# Wetterstation.net
KiCad netlist of a schematic drawn in EAGLE
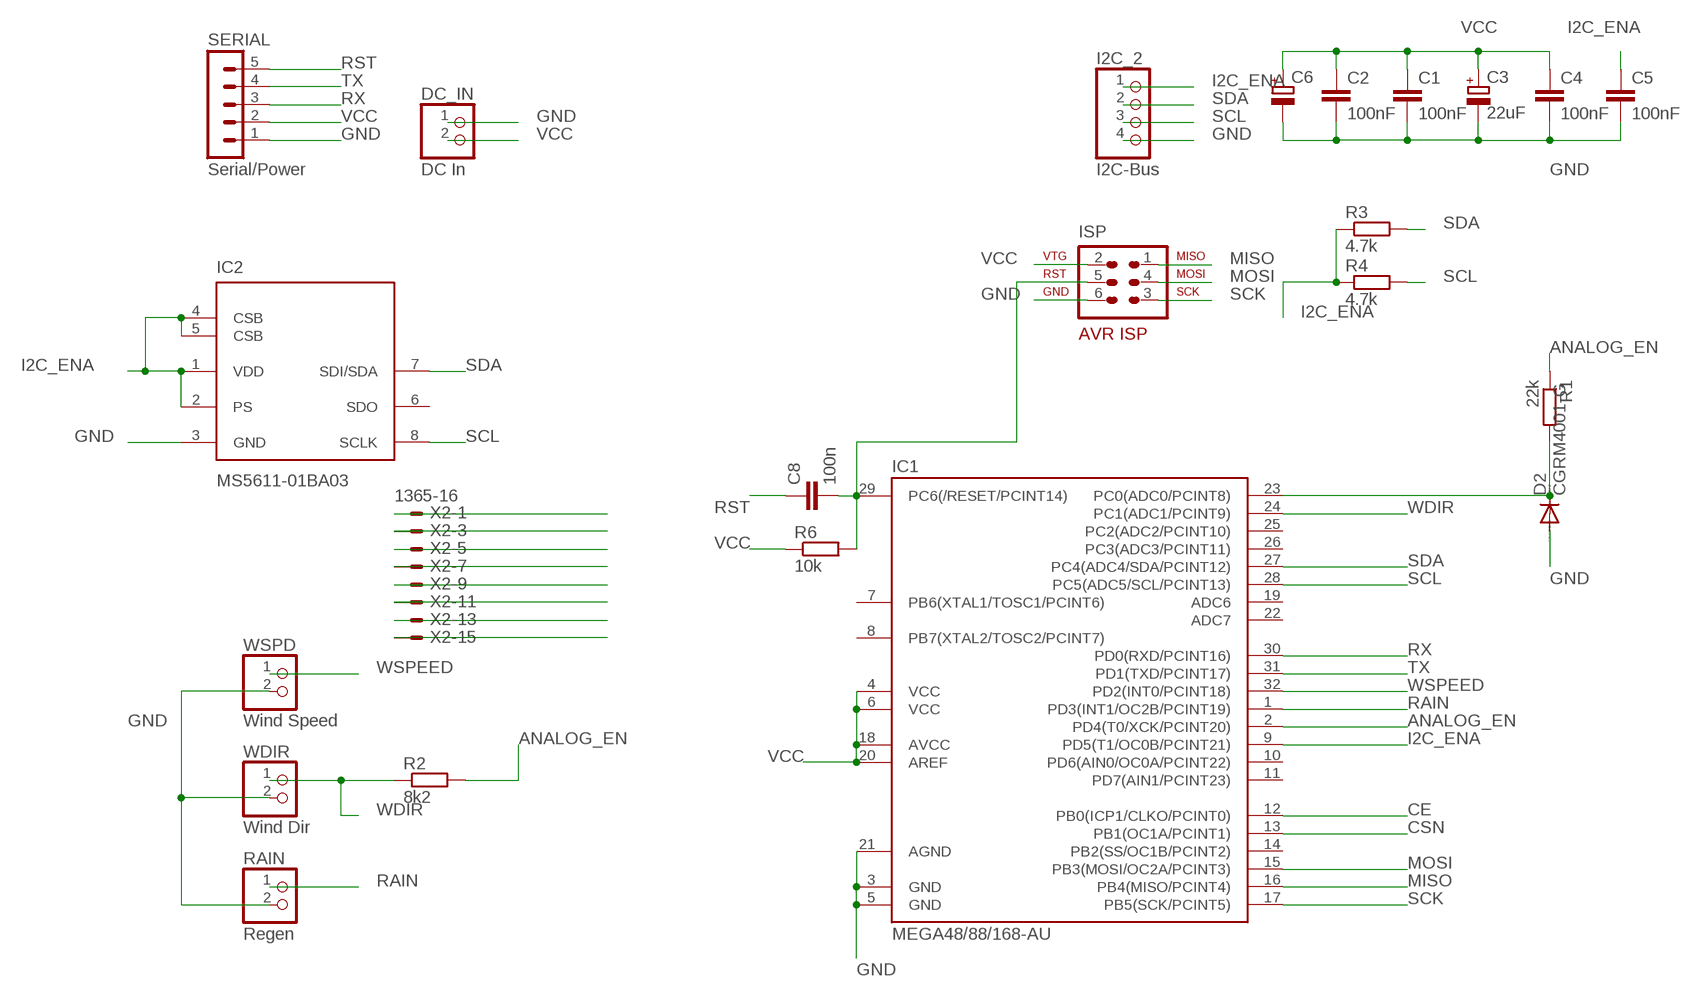
[diagram p0: schematic, sheet 1]

(export (version "E")
  (design (tool "Eeschema 10.0.6"))
  (components
    (comp (ref "C1")
      (value "100nF")
      (footprint "eagle-import:C0805")
      (libsource (lib "eagle-import") (part "C-EUC0805"))
    )
    (comp (ref "C2")
      (value "100nF")
      (footprint "eagle-import:C0805")
      (libsource (lib "eagle-import") (part "C-EUC0805"))
    )
    (comp (ref "C3")
      (value "22uF")
      (footprint "eagle-import:SMC_C")
      (libsource (lib "eagle-import") (part "resistor_CPOL-EUSMCC"))
    )
    (comp (ref "C4")
      (value "100nF")
      (footprint "eagle-import:C0805")
      (libsource (lib "eagle-import") (part "C-EUC0805"))
    )
    (comp (ref "C5")
      (value "100nF")
      (footprint "eagle-import:C0805")
      (libsource (lib "eagle-import") (part "C-EUC0805"))
    )
    (comp (ref "C6")
      (value "CPOL-EUB/3528-21R")
      (footprint "eagle-import:B_3528-21R")
      (libsource (lib "eagle-import") (part "CPOL-EUB/3528-21R"))
    )
    (comp (ref "C8")
      (value "100n")
      (footprint "eagle-import:C0805")
      (libsource (lib "eagle-import") (part "C-EUC0805"))
    )
    (comp (ref "D2")
      (value "CGRM4001-G")
      (footprint "eagle-import:SOD-123_MINI-SMA")
      (libsource (lib "eagle-import") (part "CGRM400-G1"))
    )
    (comp (ref "DC_IN")
      (value "DC In")
      (footprint "eagle-import:1X02")
      (libsource (lib "eagle-import") (part "PINHD-1X2"))
    )
    (comp (ref "I2C_2")
      (value "I2C-Bus")
      (footprint "eagle-import:1X04")
      (libsource (lib "eagle-import") (part "PINHD-1X4"))
    )
    (comp (ref "IC1")
      (value "MEGA48/88/168-AU")
      (footprint "eagle-import:TQFP32-08")
      (libsource (lib "eagle-import") (part "MEGA48/88/168-AU"))
    )
    (comp (ref "IC2")
      (value "MS5611-01BA03")
      (footprint "eagle-import:SON125P300X500X100-8N")
      (libsource (lib "eagle-import") (part "MS5611-01BA03"))
    )
    (comp (ref "ISP")
      (value "AVR-ISP-6")
      (footprint "eagle-import:AVR-ISP-6")
      (libsource (lib "eagle-import") (part "AVR-ISP-6"))
    )
    (comp (ref "R1")
      (value "22k")
      (footprint "eagle-import:R1206")
      (libsource (lib "eagle-import") (part "R-EU_R1206"))
    )
    (comp (ref "R2")
      (value "8k2")
      (footprint "eagle-import:R1206")
      (libsource (lib "eagle-import") (part "R-EU_R1206"))
    )
    (comp (ref "R3")
      (value "4.7k")
      (footprint "eagle-import:R1206")
      (libsource (lib "eagle-import") (part "R-EU_R1206"))
    )
    (comp (ref "R4")
      (value "4.7k")
      (footprint "eagle-import:R1206")
      (libsource (lib "eagle-import") (part "R-EU_R1206"))
    )
    (comp (ref "R6")
      (value "10k")
      (footprint "eagle-import:R1206")
      (libsource (lib "eagle-import") (part "R-EU_R1206"))
    )
    (comp (ref "RAIN")
      (value "Regen")
      (footprint "eagle-import:1X02")
      (libsource (lib "eagle-import") (part "PINHD-1X2"))
    )
    (comp (ref "SERIAL")
      (value "Serial/Power")
      (footprint "eagle-import:MA05-1")
      (libsource (lib "eagle-import") (part "MA05-1"))
    )
    (comp (ref "WDIR")
      (value "Wind Dir")
      (footprint "eagle-import:1X02")
      (libsource (lib "eagle-import") (part "PINHD-1X2"))
    )
    (comp (ref "WSPD")
      (value "Wind Speed")
      (footprint "eagle-import:1X02")
      (libsource (lib "eagle-import") (part "PINHD-1X2"))
    )
    (comp (ref "X2")
      (value "1365-16")
      (footprint "eagle-import:1365-16")
      (libsource (lib "eagle-import") (part "1365-16"))
    )
  )
  (nets
    (net (code "1") (name "/ANALOG_EN") (class "Default")
      (node (ref "IC1") (pin "2") (pinfunction "PD4(T0/XCK/PCINT20)_2") (pintype "bidirectional"))
      (node (ref "R1") (pin "1") (pinfunction "1_1") (pintype "passive"))
      (node (ref "R2") (pin "2") (pinfunction "2_2") (pintype "passive"))
    )
    (net (code "2") (name "/CE") (class "Default")
      (node (ref "IC1") (pin "12") (pinfunction "PB0(ICP1/CLKO/PCINT0)_12") (pintype "bidirectional"))
      (node (ref "X2") (pin "3") (pinfunction "S_3") (pintype "passive"))
    )
    (net (code "3") (name "/CSN") (class "Default")
      (node (ref "IC1") (pin "13") (pinfunction "PB1(OC1A/PCINT1)_13") (pintype "bidirectional"))
      (node (ref "X2") (pin "5") (pinfunction "S_5") (pintype "passive"))
    )
    (net (code "4") (name "/GND") (class "Default")
      (node (ref "C1") (pin "2") (pinfunction "2_2") (pintype "passive"))
      (node (ref "C2") (pin "2") (pinfunction "2_2") (pintype "passive"))
      (node (ref "C3") (pin "-") (pinfunction "-_-") (pintype "passive"))
      (node (ref "C4") (pin "2") (pinfunction "2_2") (pintype "passive"))
      (node (ref "C5") (pin "2") (pinfunction "2_2") (pintype "passive"))
      (node (ref "C6") (pin "-") (pinfunction "-_-") (pintype "passive"))
      (node (ref "D2") (pin "A") (pinfunction "A_A") (pintype "passive"))
      (node (ref "DC_IN") (pin "1") (pinfunction "1_1") (pintype "passive"))
      (node (ref "I2C_2") (pin "4") (pinfunction "4_4") (pintype "passive"))
      (node (ref "IC1") (pin "21") (pinfunction "AGND_21") (pintype "power_in"))
      (node (ref "IC1") (pin "3") (pinfunction "GND_3") (pintype "power_in"))
      (node (ref "IC1") (pin "5") (pinfunction "GND_5") (pintype "power_in"))
      (node (ref "IC2") (pin "3") (pinfunction "GND_3") (pintype "power_in"))
      (node (ref "ISP") (pin "6") (pinfunction "6_6") (pintype "passive"))
      (node (ref "RAIN") (pin "2") (pinfunction "2_2") (pintype "passive"))
      (node (ref "SERIAL") (pin "1") (pinfunction "1_1") (pintype "passive"))
      (node (ref "WDIR") (pin "2") (pinfunction "2_2") (pintype "passive"))
      (node (ref "WSPD") (pin "2") (pinfunction "2_2") (pintype "passive"))
      (node (ref "X2") (pin "15") (pinfunction "S_15") (pintype "passive"))
    )
    (net (code "5") (name "/I2C_ENA") (class "Default")
      (node (ref "C5") (pin "1") (pinfunction "1_1") (pintype "passive"))
      (node (ref "I2C_2") (pin "1") (pinfunction "1_1") (pintype "passive"))
      (node (ref "IC1") (pin "9") (pinfunction "PD5(T1/OC0B/PCINT21)_9") (pintype "bidirectional"))
      (node (ref "IC2") (pin "1") (pinfunction "VDD_1") (pintype "power_in"))
      (node (ref "IC2") (pin "2") (pinfunction "PS_2") (pintype "input"))
      (node (ref "IC2") (pin "4") (pinfunction "CSB_4") (pintype "input"))
      (node (ref "IC2") (pin "5") (pinfunction "CSB_5") (pintype "input"))
      (node (ref "R3") (pin "1") (pinfunction "1_1") (pintype "passive"))
      (node (ref "R4") (pin "1") (pinfunction "1_1") (pintype "passive"))
    )
    (net (code "6") (name "/MISO") (class "Default")
      (node (ref "IC1") (pin "16") (pinfunction "PB4(MISO/PCINT4)_16") (pintype "bidirectional"))
      (node (ref "ISP") (pin "1") (pinfunction "1_1") (pintype "passive"))
      (node (ref "X2") (pin "11") (pinfunction "S_11") (pintype "passive"))
    )
    (net (code "7") (name "/MOSI") (class "Default")
      (node (ref "IC1") (pin "15") (pinfunction "PB3(MOSI/OC2A/PCINT3)_15") (pintype "bidirectional"))
      (node (ref "ISP") (pin "4") (pinfunction "4_4") (pintype "passive"))
      (node (ref "X2") (pin "9") (pinfunction "S_9") (pintype "passive"))
    )
    (net (code "8") (name "/RAIN") (class "Default")
      (node (ref "IC1") (pin "1") (pinfunction "PD3(INT1/OC2B/PCINT19)_1") (pintype "bidirectional"))
      (node (ref "RAIN") (pin "1") (pinfunction "1_1") (pintype "passive"))
    )
    (net (code "9") (name "/RST") (class "Default")
      (node (ref "C8") (pin "1") (pinfunction "1_1") (pintype "passive"))
      (node (ref "SERIAL") (pin "5") (pinfunction "5_5") (pintype "passive"))
    )
    (net (code "10") (name "/RX") (class "Default")
      (node (ref "IC1") (pin "30") (pinfunction "PD0(RXD/PCINT16)_30") (pintype "bidirectional"))
      (node (ref "SERIAL") (pin "3") (pinfunction "3_3") (pintype "passive"))
    )
    (net (code "11") (name "/SCK") (class "Default")
      (node (ref "IC1") (pin "17") (pinfunction "PB5(SCK/PCINT5)_17") (pintype "bidirectional"))
      (node (ref "ISP") (pin "3") (pinfunction "3_3") (pintype "passive"))
      (node (ref "X2") (pin "7") (pinfunction "S_7") (pintype "passive"))
    )
    (net (code "12") (name "/SCL") (class "Default")
      (node (ref "I2C_2") (pin "3") (pinfunction "3_3") (pintype "passive"))
      (node (ref "IC1") (pin "28") (pinfunction "PC5(ADC5/SCL/PCINT13)_28") (pintype "bidirectional"))
      (node (ref "IC2") (pin "8") (pinfunction "SCLK_8") (pintype "input"))
      (node (ref "R4") (pin "2") (pinfunction "2_2") (pintype "passive"))
    )
    (net (code "13") (name "/SDA") (class "Default")
      (node (ref "I2C_2") (pin "2") (pinfunction "2_2") (pintype "passive"))
      (node (ref "IC1") (pin "27") (pinfunction "PC4(ADC4/SDA/PCINT12)_27") (pintype "bidirectional"))
      (node (ref "IC2") (pin "7") (pinfunction "SDI/SDA_7") (pintype "bidirectional"))
      (node (ref "R3") (pin "2") (pinfunction "2_2") (pintype "passive"))
    )
    (net (code "14") (name "/TX") (class "Default")
      (node (ref "IC1") (pin "31") (pinfunction "PD1(TXD/PCINT17)_31") (pintype "bidirectional"))
      (node (ref "SERIAL") (pin "4") (pinfunction "4_4") (pintype "passive"))
    )
    (net (code "15") (name "/VCC") (class "Default")
      (node (ref "C1") (pin "1") (pinfunction "1_1") (pintype "passive"))
      (node (ref "C2") (pin "1") (pinfunction "1_1") (pintype "passive"))
      (node (ref "C3") (pin "+") (pinfunction "+_+") (pintype "passive"))
      (node (ref "C4") (pin "1") (pinfunction "1_1") (pintype "passive"))
      (node (ref "C6") (pin "+") (pinfunction "+_+") (pintype "passive"))
      (node (ref "DC_IN") (pin "2") (pinfunction "2_2") (pintype "passive"))
      (node (ref "IC1") (pin "18") (pinfunction "AVCC_18") (pintype "passive"))
      (node (ref "IC1") (pin "20") (pinfunction "AREF_20") (pintype "passive"))
      (node (ref "IC1") (pin "4") (pinfunction "VCC_4") (pintype "power_in"))
      (node (ref "IC1") (pin "6") (pinfunction "VCC_6") (pintype "power_in"))
      (node (ref "ISP") (pin "2") (pinfunction "2_2") (pintype "passive"))
      (node (ref "R6") (pin "1") (pinfunction "1_1") (pintype "passive"))
      (node (ref "SERIAL") (pin "2") (pinfunction "2_2") (pintype "passive"))
      (node (ref "X2") (pin "1") (pinfunction "S_1") (pintype "passive"))
    )
    (net (code "16") (name "/WDIR") (class "Default")
      (node (ref "IC1") (pin "24") (pinfunction "PC1(ADC1/PCINT9)_24") (pintype "bidirectional"))
      (node (ref "R2") (pin "1") (pinfunction "1_1") (pintype "passive"))
      (node (ref "WDIR") (pin "1") (pinfunction "1_1") (pintype "passive"))
    )
    (net (code "17") (name "/WSPEED") (class "Default")
      (node (ref "IC1") (pin "32") (pinfunction "PD2(INT0/PCINT18)_32") (pintype "bidirectional"))
      (node (ref "WSPD") (pin "1") (pinfunction "1_1") (pintype "passive"))
    )
    (net (code "18") (name "Net-(IC1-PC0(ADC0{slash}PCINT8))") (class "Default")
      (node (ref "D2") (pin "C") (pinfunction "C_C") (pintype "passive"))
      (node (ref "IC1") (pin "23") (pinfunction "PC0(ADC0/PCINT8)_23") (pintype "bidirectional"))
      (node (ref "R1") (pin "2") (pinfunction "2_2") (pintype "passive"))
    )
    (net (code "19") (name "Net-(IC1-PC6({slash}RESET{slash}PCINT14))") (class "Default")
      (node (ref "C8") (pin "2") (pinfunction "2_2") (pintype "passive"))
      (node (ref "IC1") (pin "29") (pinfunction "PC6(/RESET/PCINT14)_29") (pintype "bidirectional"))
      (node (ref "ISP") (pin "5") (pinfunction "5_5") (pintype "passive"))
      (node (ref "R6") (pin "2") (pinfunction "2_2") (pintype "passive"))
    )
    (net (code "20") (name "unconnected-(IC1-ADC6-Pad19)") (class "Default")
      (node (ref "IC1") (pin "19") (pinfunction "ADC6_19") (pintype "passive"))
    )
    (net (code "21") (name "unconnected-(IC1-ADC7-Pad22)") (class "Default")
      (node (ref "IC1") (pin "22") (pinfunction "ADC7_22") (pintype "passive"))
    )
    (net (code "22") (name "unconnected-(IC1-PB2(SS{slash}OC1B{slash}PCINT2)-Pad14)") (class "Default")
      (node (ref "IC1") (pin "14") (pinfunction "PB2(SS/OC1B/PCINT2)_14") (pintype "bidirectional"))
    )
    (net (code "23") (name "unconnected-(IC1-PB6(XTAL1{slash}TOSC1{slash}PCINT6)-Pad7)") (class "Default")
      (node (ref "IC1") (pin "7") (pinfunction "PB6(XTAL1/TOSC1/PCINT6)_7") (pintype "bidirectional"))
    )
    (net (code "24") (name "unconnected-(IC1-PB7(XTAL2{slash}TOSC2{slash}PCINT7)-Pad8)") (class "Default")
      (node (ref "IC1") (pin "8") (pinfunction "PB7(XTAL2/TOSC2/PCINT7)_8") (pintype "bidirectional"))
    )
    (net (code "25") (name "unconnected-(IC1-PC2(ADC2{slash}PCINT10)-Pad25)") (class "Default")
      (node (ref "IC1") (pin "25") (pinfunction "PC2(ADC2/PCINT10)_25") (pintype "bidirectional"))
    )
    (net (code "26") (name "unconnected-(IC1-PC3(ADC3{slash}PCINT11)-Pad26)") (class "Default")
      (node (ref "IC1") (pin "26") (pinfunction "PC3(ADC3/PCINT11)_26") (pintype "bidirectional"))
    )
    (net (code "27") (name "unconnected-(IC1-PD6(AIN0{slash}OC0A{slash}PCINT22)-Pad10)") (class "Default")
      (node (ref "IC1") (pin "10") (pinfunction "PD6(AIN0/OC0A/PCINT22)_10") (pintype "bidirectional"))
    )
    (net (code "28") (name "unconnected-(IC1-PD7(AIN1{slash}PCINT23)-Pad11)") (class "Default")
      (node (ref "IC1") (pin "11") (pinfunction "PD7(AIN1/PCINT23)_11") (pintype "bidirectional"))
    )
    (net (code "29") (name "unconnected-(IC2-SDO-Pad6)") (class "Default")
      (node (ref "IC2") (pin "6") (pinfunction "SDO_6") (pintype "output"))
    )
    (net (code "30") (name "unconnected-(X2E-S-Pad13)") (class "Default")
      (node (ref "X2") (pin "13") (pinfunction "S_13") (pintype "passive"))
    )
  )
)
